# SCH_USBHub_2025-12-05.net
KiCad netlist of a schematic drawn in EasyEDA
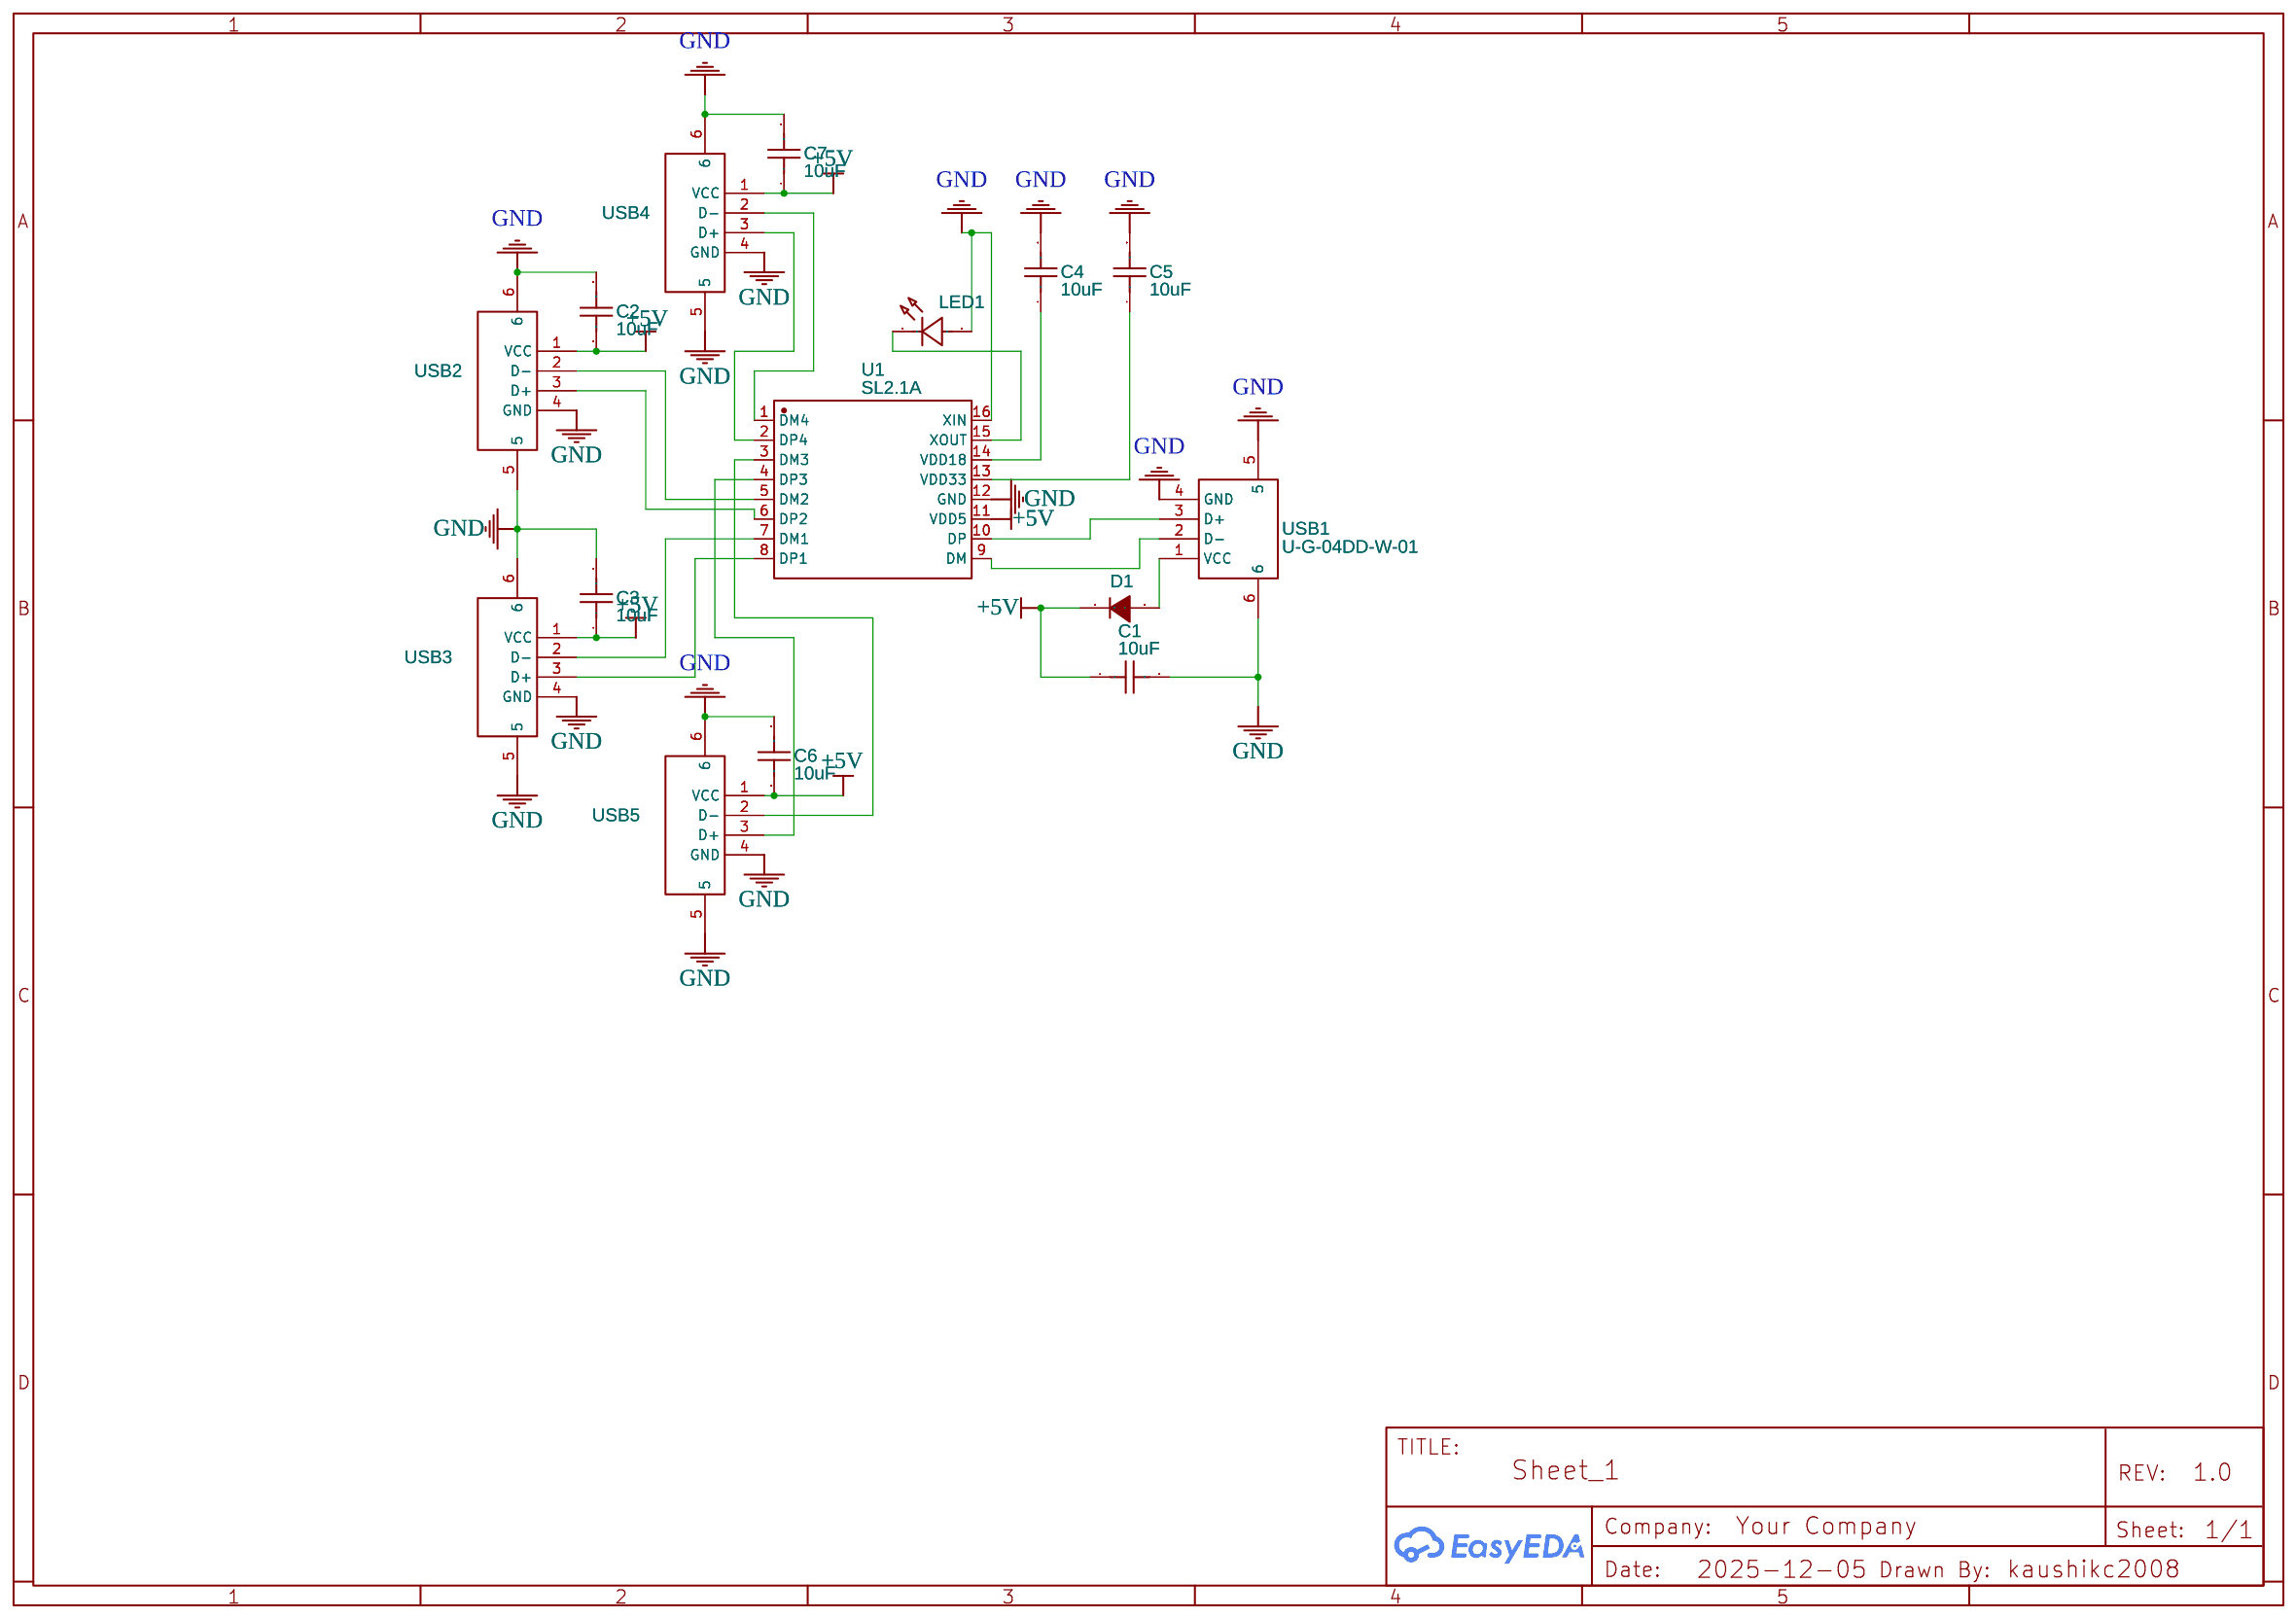
[diagram p0: schematic sheet]

(export (version "E")
  (design (tool "Eeschema 10.0.6"))
  (components
    (comp (ref "C1")
      (value "10uF")
      (fields
        (field (name "Manufacturer Part") "CL10A106KP8NNNC")
        (field (name "Manufacturer") "SAMSUNG(三星)")
      )
      (libsource (lib "") (part "CL10A106KP8NNNC_1"))
    )
    (comp (ref "C2")
      (value "10uF")
      (fields
        (field (name "Manufacturer Part") "CL10A106KP8NNNC")
        (field (name "Manufacturer") "SAMSUNG(三星)")
      )
      (libsource (lib "") (part "CL10A106KP8NNNC"))
    )
    (comp (ref "C3")
      (value "10uF")
      (fields
        (field (name "Manufacturer Part") "CL10A106KP8NNNC")
        (field (name "Manufacturer") "SAMSUNG(三星)")
      )
      (libsource (lib "") (part "CL10A106KP8NNNC"))
    )
    (comp (ref "C4")
      (value "10uF")
      (fields
        (field (name "Manufacturer Part") "CL10A106KP8NNNC")
        (field (name "Manufacturer") "SAMSUNG(三星)")
      )
      (libsource (lib "") (part "CL10A106KP8NNNC"))
    )
    (comp (ref "C5")
      (value "10uF")
      (fields
        (field (name "Manufacturer Part") "CL10A106KP8NNNC")
        (field (name "Manufacturer") "SAMSUNG(三星)")
      )
      (libsource (lib "") (part "CL10A106KP8NNNC"))
    )
    (comp (ref "C6")
      (value "10uF")
      (fields
        (field (name "Manufacturer Part") "CL10A106KP8NNNC")
        (field (name "Manufacturer") "SAMSUNG(三星)")
      )
      (libsource (lib "") (part "CL10A106KP8NNNC"))
    )
    (comp (ref "C7")
      (value "10uF")
      (fields
        (field (name "Manufacturer Part") "CL10A106KP8NNNC")
        (field (name "Manufacturer") "SAMSUNG(三星)")
      )
      (libsource (lib "") (part "CL10A106KP8NNNC"))
    )
    (comp (ref "D1")
      (value "NSR0320MW2T1G")
      (fields (field (name "Manufacturer") "onsemi(安森美)"))
      (libsource (lib "") (part "NSR0320MW2T1G"))
    )
    (comp (ref "LED1")
      (value "XL-502UWC")
      (fields (field (name "Manufacturer") "XINGLIGHT(成兴光)"))
      (libsource (lib "") (part "XL-502UWC"))
    )
    (comp (ref "U1")
      (value "SL2.1A")
      (fields (field (name "Manufacturer") "CoreChips(和芯润德)"))
      (libsource (lib "") (part "SL2.1A"))
    )
    (comp (ref "USB1")
      (value "U-G-04DD-W-01")
      (fields (field (name "Manufacturer Part") "U-G-O4DD-W-1") (field (name "Manufacturer") "韩国韩荣"))
      (libsource (lib "") (part "U-G-04DD-W-01"))
    )
    (comp (ref "USB2")
      (value "USB-AF-90-14.4X13.6-H7.0-DIP")
      (fields (field (name "Manufacturer Part") "903-131A1011D10100") (field (name "Manufacturer") "精拓金"))
      (libsource (lib "") (part "USB-AF-90-14.4X13.6-H7.0-DIP"))
    )
    (comp (ref "USB3")
      (value "USB-AF-90-14.4X13.6-H7.0-DIP")
      (fields (field (name "Manufacturer Part") "903-131A1011D10100") (field (name "Manufacturer") "精拓金"))
      (libsource (lib "") (part "USB-AF-90-14.4X13.6-H7.0-DIP"))
    )
    (comp (ref "USB4")
      (value "USB-AF-90-14.4X13.6-H7.0-DIP")
      (fields (field (name "Manufacturer Part") "903-131A1011D10100") (field (name "Manufacturer") "精拓金"))
      (libsource (lib "") (part "USB-AF-90-14.4X13.6-H7.0-DIP"))
    )
    (comp (ref "USB5")
      (value "USB-AF-90-14.4X13.6-H7.0-DIP")
      (fields (field (name "Manufacturer Part") "903-131A1011D10100") (field (name "Manufacturer") "精拓金"))
      (libsource (lib "") (part "USB-AF-90-14.4X13.6-H7.0-DIP"))
    )
  )
  (nets
    (net (code "1") (name "+5V") (class "Default")
      (node (ref "C1") (pin "1") (pinfunction "1_1") (pintype "unspecified"))
      (node (ref "C2") (pin "1") (pinfunction "1_1") (pintype "unspecified"))
      (node (ref "C3") (pin "1") (pinfunction "1_1") (pintype "unspecified"))
      (node (ref "C6") (pin "1") (pinfunction "1_1") (pintype "unspecified"))
      (node (ref "C7") (pin "1") (pinfunction "1_1") (pintype "unspecified"))
      (node (ref "D1") (pin "1") (pinfunction "C_1") (pintype "unspecified"))
      (node (ref "U1") (pin "11") (pinfunction "VDD5_11") (pintype "unspecified"))
      (node (ref "USB2") (pin "1") (pinfunction "VCC_1") (pintype "unspecified"))
      (node (ref "USB3") (pin "1") (pinfunction "VCC_1") (pintype "unspecified"))
      (node (ref "USB4") (pin "1") (pinfunction "VCC_1") (pintype "unspecified"))
      (node (ref "USB5") (pin "1") (pinfunction "VCC_1") (pintype "unspecified"))
    )
    (net (code "2") (name "GND") (class "Default")
      (node (ref "C1") (pin "2") (pinfunction "2_2") (pintype "unspecified"))
      (node (ref "C2") (pin "2") (pinfunction "2_2") (pintype "unspecified"))
      (node (ref "C3") (pin "2") (pinfunction "2_2") (pintype "unspecified"))
      (node (ref "C4") (pin "2") (pinfunction "2_2") (pintype "unspecified"))
      (node (ref "C5") (pin "2") (pinfunction "2_2") (pintype "unspecified"))
      (node (ref "C6") (pin "2") (pinfunction "2_2") (pintype "unspecified"))
      (node (ref "C7") (pin "2") (pinfunction "2_2") (pintype "unspecified"))
      (node (ref "LED1") (pin "2") (pinfunction "A_2") (pintype "unspecified"))
      (node (ref "U1") (pin "12") (pinfunction "GND_12") (pintype "unspecified"))
      (node (ref "U1") (pin "16") (pinfunction "XIN_16") (pintype "unspecified"))
      (node (ref "USB1") (pin "4") (pinfunction "GND_4") (pintype "unspecified"))
      (node (ref "USB1") (pin "5") (pinfunction "5_5") (pintype "unspecified"))
      (node (ref "USB1") (pin "6") (pinfunction "6_6") (pintype "unspecified"))
      (node (ref "USB2") (pin "4") (pinfunction "GND_4") (pintype "unspecified"))
      (node (ref "USB2") (pin "5") (pinfunction "5_5") (pintype "unspecified"))
      (node (ref "USB2") (pin "6") (pinfunction "6_6") (pintype "unspecified"))
      (node (ref "USB3") (pin "4") (pinfunction "GND_4") (pintype "unspecified"))
      (node (ref "USB3") (pin "5") (pinfunction "5_5") (pintype "unspecified"))
      (node (ref "USB3") (pin "6") (pinfunction "6_6") (pintype "unspecified"))
      (node (ref "USB4") (pin "4") (pinfunction "GND_4") (pintype "unspecified"))
      (node (ref "USB4") (pin "5") (pinfunction "5_5") (pintype "unspecified"))
      (node (ref "USB4") (pin "6") (pinfunction "6_6") (pintype "unspecified"))
      (node (ref "USB5") (pin "4") (pinfunction "GND_4") (pintype "unspecified"))
      (node (ref "USB5") (pin "5") (pinfunction "5_5") (pintype "unspecified"))
      (node (ref "USB5") (pin "6") (pinfunction "6_6") (pintype "unspecified"))
    )
    (net (code "3") (name "Net-(D1-A)") (class "Default")
      (node (ref "D1") (pin "2") (pinfunction "A_2") (pintype "unspecified"))
      (node (ref "USB1") (pin "1") (pinfunction "VCC_1") (pintype "unspecified"))
    )
    (net (code "4") (name "Net-(LED1-K)") (class "Default")
      (node (ref "LED1") (pin "1") (pinfunction "K_1") (pintype "unspecified"))
      (node (ref "U1") (pin "15") (pinfunction "XOUT_15") (pintype "unspecified"))
    )
    (net (code "5") (name "Net-(U1-DM)") (class "Default")
      (node (ref "U1") (pin "9") (pinfunction "DM_9") (pintype "unspecified"))
      (node (ref "USB1") (pin "2") (pinfunction "D-_2") (pintype "unspecified"))
    )
    (net (code "6") (name "Net-(U1-DM1)") (class "Default")
      (node (ref "U1") (pin "7") (pinfunction "DM1_7") (pintype "unspecified"))
      (node (ref "USB3") (pin "2") (pinfunction "D-_2") (pintype "unspecified"))
    )
    (net (code "7") (name "Net-(U1-DM2)") (class "Default")
      (node (ref "U1") (pin "5") (pinfunction "DM2_5") (pintype "unspecified"))
      (node (ref "USB2") (pin "2") (pinfunction "D-_2") (pintype "unspecified"))
    )
    (net (code "8") (name "Net-(U1-DM3)") (class "Default")
      (node (ref "U1") (pin "3") (pinfunction "DM3_3") (pintype "unspecified"))
      (node (ref "USB5") (pin "2") (pinfunction "D-_2") (pintype "unspecified"))
    )
    (net (code "9") (name "Net-(U1-DM4)") (class "Default")
      (node (ref "U1") (pin "1") (pinfunction "DM4_1") (pintype "unspecified"))
      (node (ref "USB4") (pin "2") (pinfunction "D-_2") (pintype "unspecified"))
    )
    (net (code "10") (name "Net-(U1-DP)") (class "Default")
      (node (ref "U1") (pin "10") (pinfunction "DP_10") (pintype "unspecified"))
      (node (ref "USB1") (pin "3") (pinfunction "D+_3") (pintype "unspecified"))
    )
    (net (code "11") (name "Net-(U1-DP1)") (class "Default")
      (node (ref "U1") (pin "8") (pinfunction "DP1_8") (pintype "unspecified"))
      (node (ref "USB3") (pin "3") (pinfunction "D+_3") (pintype "unspecified"))
    )
    (net (code "12") (name "Net-(U1-DP2)") (class "Default")
      (node (ref "U1") (pin "6") (pinfunction "DP2_6") (pintype "unspecified"))
      (node (ref "USB2") (pin "3") (pinfunction "D+_3") (pintype "unspecified"))
    )
    (net (code "13") (name "Net-(U1-DP3)") (class "Default")
      (node (ref "U1") (pin "4") (pinfunction "DP3_4") (pintype "unspecified"))
      (node (ref "USB5") (pin "3") (pinfunction "D+_3") (pintype "unspecified"))
    )
    (net (code "14") (name "Net-(U1-DP4)") (class "Default")
      (node (ref "U1") (pin "2") (pinfunction "DP4_2") (pintype "unspecified"))
      (node (ref "USB4") (pin "3") (pinfunction "D+_3") (pintype "unspecified"))
    )
    (net (code "15") (name "Net-(U1-VDD18)") (class "Default")
      (node (ref "C4") (pin "1") (pinfunction "1_1") (pintype "unspecified"))
      (node (ref "U1") (pin "14") (pinfunction "VDD18_14") (pintype "unspecified"))
    )
    (net (code "16") (name "Net-(U1-VDD33)") (class "Default")
      (node (ref "C5") (pin "1") (pinfunction "1_1") (pintype "unspecified"))
      (node (ref "U1") (pin "13") (pinfunction "VDD33_13") (pintype "unspecified"))
    )
  )
)
